# UpperMotor.net
KiCad netlist of a schematic drawn in EasyEDA Pro
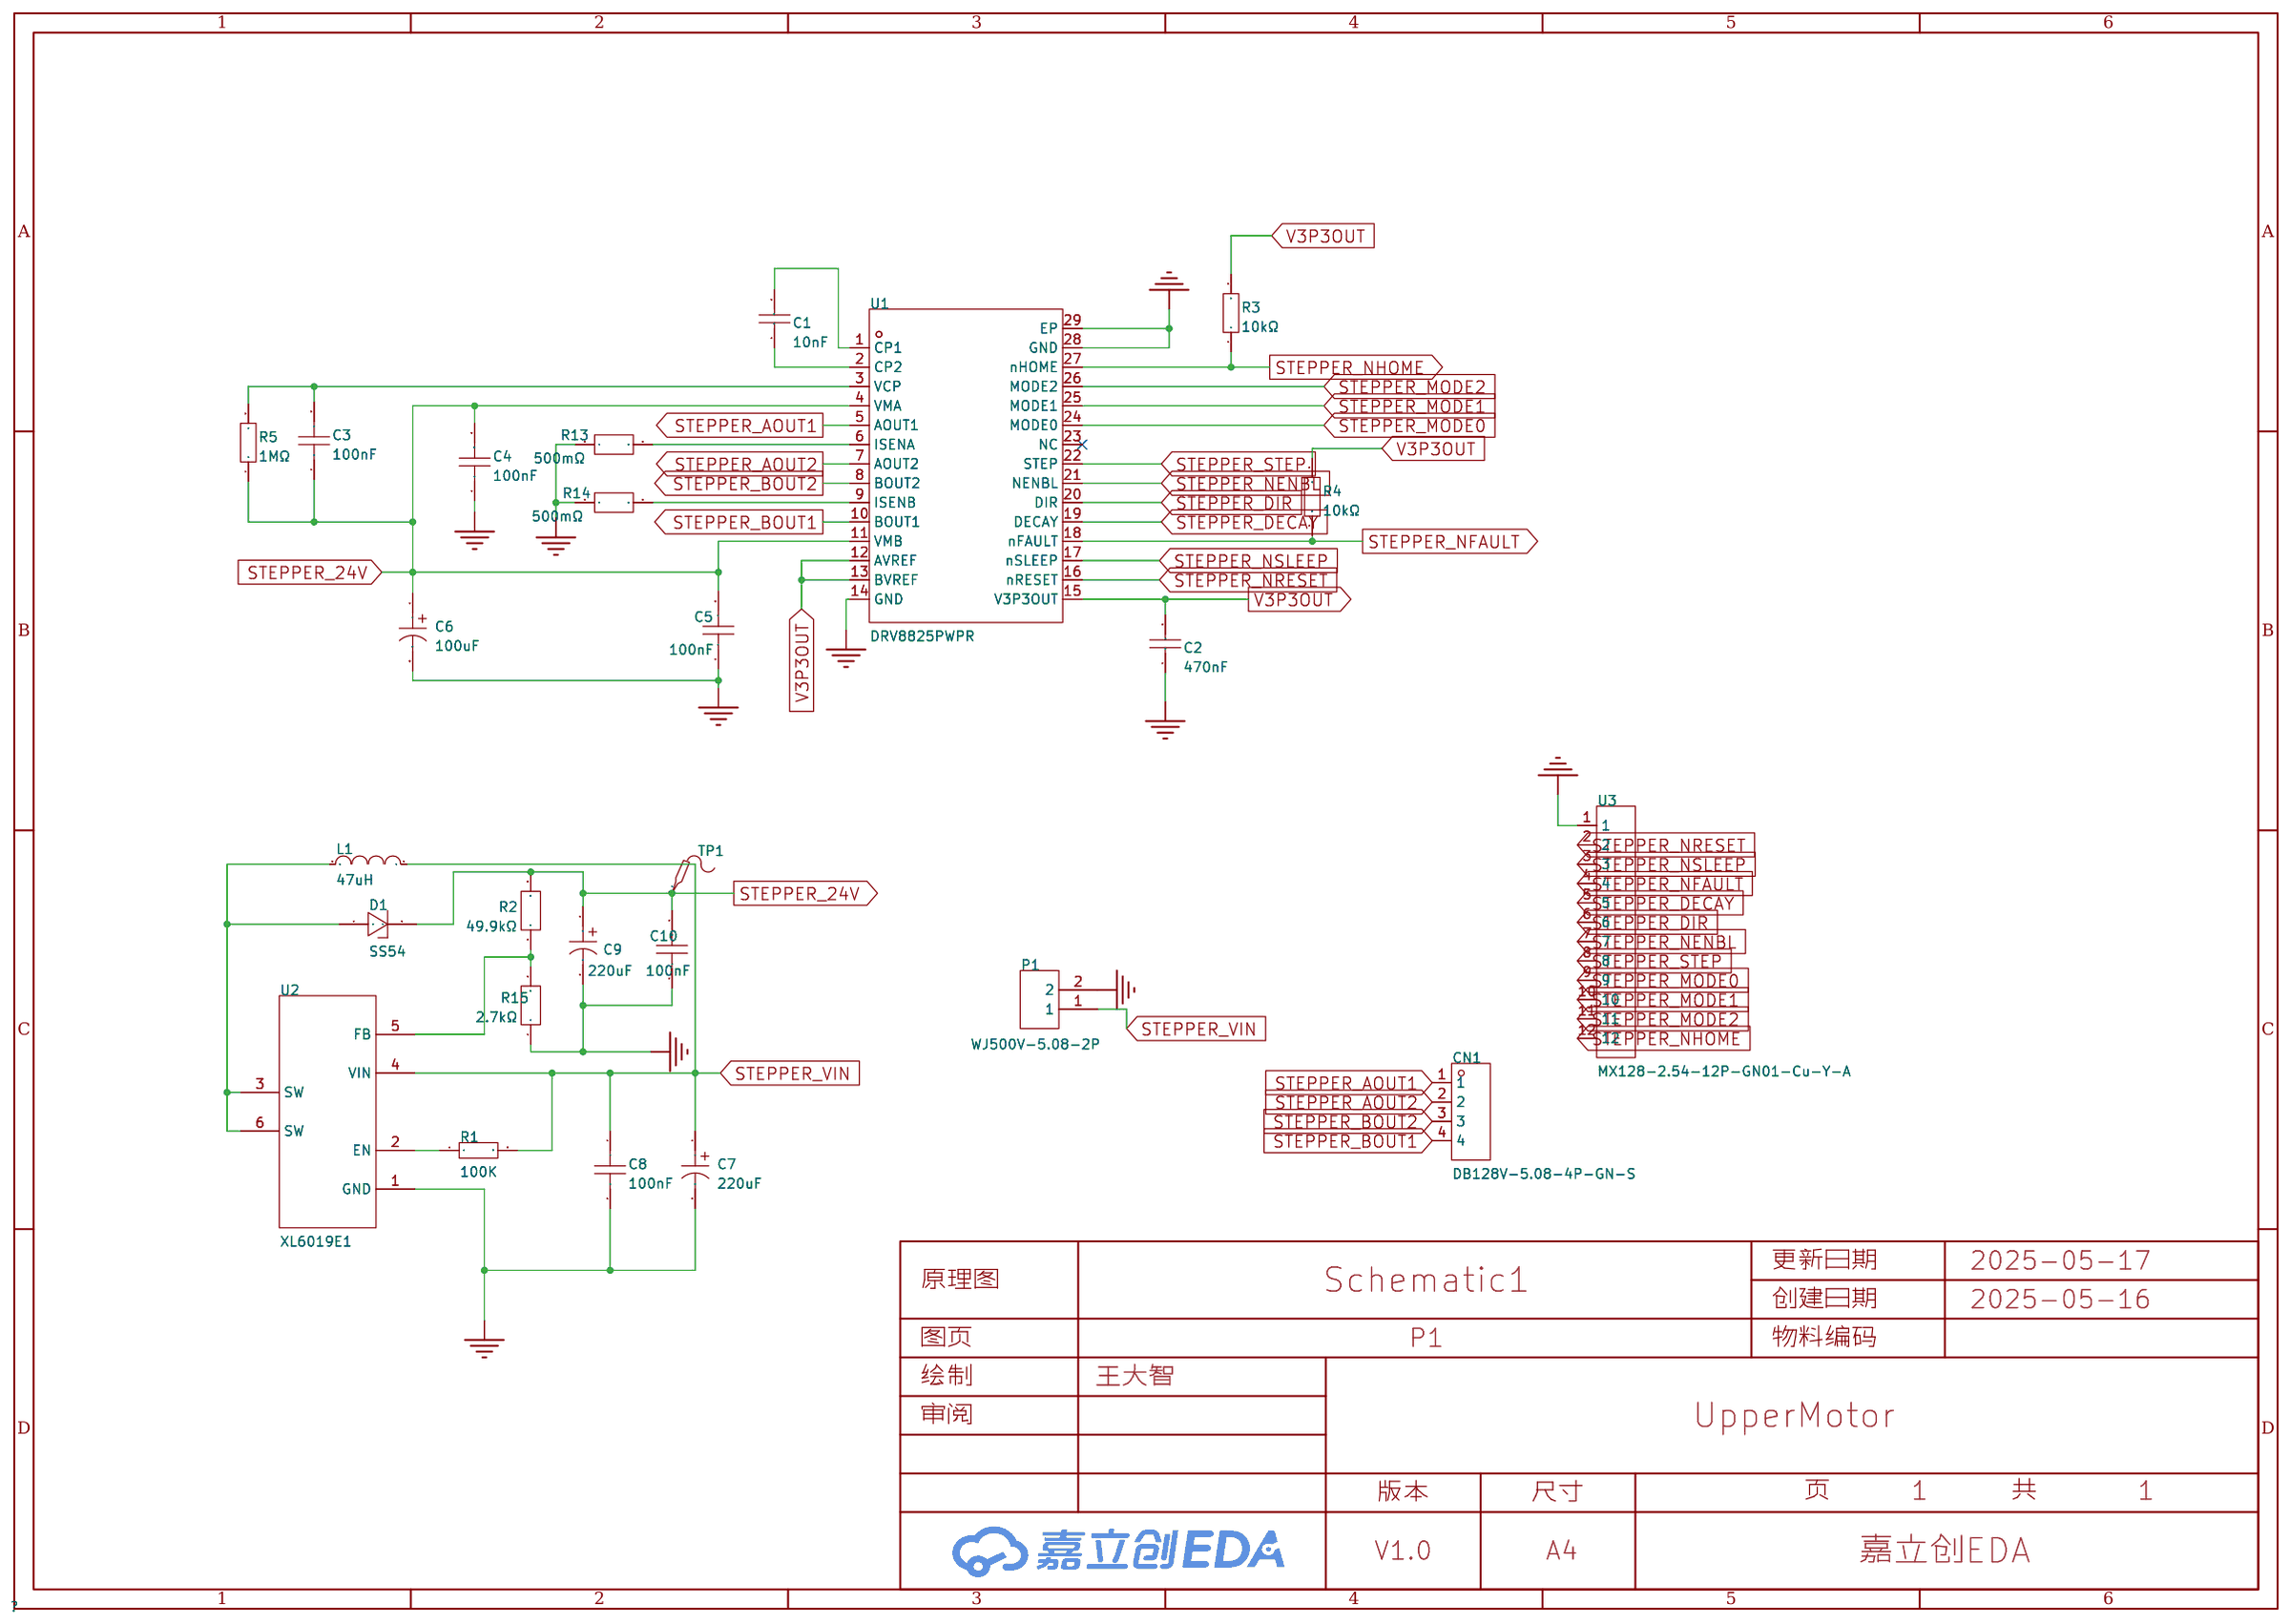
[diagram p0: schematic sheet]

(export (version "E")
  (design (tool "Eeschema 10.0.6"))
  (components
    (comp (ref "C1")
      (value "10nF")
      (footprint "easyedapro:C0603")
      (description "容值:10nF;精度:±10%;额定电压:50V;材质(温度系数):X7R;")
      (fields
        (field (name "Manufacturer Part") "CL10B103KB8NNNC")
        (field (name "Manufacturer") "SAMSUNG(三星)")
      )
      (libsource (lib "easyedapro") (part "CL10B103KB8NNNC"))
    )
    (comp (ref "C2")
      (value "470nF")
      (footprint "easyedapro:C0603")
      (description "容值:470nF;精度:±10%;额定电压:25V;材质(温度系数):X7R;")
      (fields
        (field (name "Manufacturer Part") "CL10B474KA8NNNC")
        (field (name "Manufacturer") "SAMSUNG(三星)")
      )
      (libsource (lib "easyedapro") (part "CL10B474KA8NNNC"))
    )
    (comp (ref "C3")
      (value "100nF")
      (footprint "easyedapro:C0603")
      (description "容值:100nF;精度:±10%;额定电压:50V;温度系数:X7R;")
      (fields
        (field (name "Manufacturer Part") "CGA0603X7R104K500JT")
        (field (name "Manufacturer") "HRE(芯声)")
      )
      (libsource (lib "easyedapro") (part "CGA0603X7R104K500JT"))
    )
    (comp (ref "C4")
      (value "100nF")
      (footprint "easyedapro:C0603")
      (description "容值:100nF;精度:±10%;额定电压:50V;温度系数:X7R;")
      (fields
        (field (name "Manufacturer Part") "CGA0603X7R104K500JT")
        (field (name "Manufacturer") "HRE(芯声)")
      )
      (libsource (lib "easyedapro") (part "CGA0603X7R104K500JT"))
    )
    (comp (ref "C5")
      (value "100nF")
      (footprint "easyedapro:C0603")
      (description "容值:100nF;精度:±10%;额定电压:50V;温度系数:X7R;")
      (fields
        (field (name "Manufacturer Part") "CGA0603X7R104K500JT")
        (field (name "Manufacturer") "HRE(芯声)")
      )
      (libsource (lib "easyedapro") (part "CGA0603X7R104K500JT"))
    )
    (comp (ref "C6")
      (value "100uF")
      (footprint "easyedapro:CAP-SMD_BD8.1-L8.3-W8.3-LS9.3-FD")
      (description "容值:100uF;精度:±20%;额定电压:50V;纹波电流:300mA@100kHz;等效串联电阻:600mΩ@100kHz;")
      (fields
        (field (name "Manufacturer Part") "GVE1H107M0810CNVC")
        (field (name "Manufacturer") "HRK(鸿瑞凯电子)")
      )
      (libsource (lib "easyedapro") (part "GVE1H107M0810CNVC"))
    )
    (comp (ref "C7")
      (value "220uF")
      (footprint "easyedapro:CAP-SMD_BD8.0-L8.3-W8.3-FD")
      (description "容值:220uF;精度:±20%;额定电压:35V;纹波电流:175mA@120Hz;")
      (fields
        (field (name "Manufacturer Part") "GVT1V227M0810CNVC")
        (field (name "Manufacturer") "HRK(鸿瑞凯电子)")
      )
      (libsource (lib "easyedapro") (part "GVT1V227M0810CNVC"))
    )
    (comp (ref "C8")
      (value "100nF")
      (footprint "easyedapro:C0603")
      (libsource (lib "easyedapro") (part "CapAcitance"))
    )
    (comp (ref "C9")
      (value "220uF")
      (footprint "easyedapro:CAP-SMD_BD8.0-L8.3-W8.3-FD")
      (description "容值:220uF;精度:±20%;额定电压:35V;纹波电流:175mA@120Hz;")
      (fields
        (field (name "Manufacturer Part") "GVT1V227M0810CNVC")
        (field (name "Manufacturer") "HRK(鸿瑞凯电子)")
      )
      (libsource (lib "easyedapro") (part "GVT1V227M0810CNVC"))
    )
    (comp (ref "C10")
      (value "100nF")
      (footprint "easyedapro:C0603")
      (libsource (lib "easyedapro") (part "CapAcitance"))
    )
    (comp (ref "CN1")
      (value "DB128V-5.08-4P-GN-S")
      (footprint "easyedapro:CONN-TH_4P-P5.08_DIBO_DB128V-5.08")
      (fields (field (name "Manufacturer") "DORABO(地博电气)"))
      (libsource (lib "easyedapro") (part "DB128V-5.08-4P-GN-S"))
    )
    (comp (ref "D1")
      (value "SS54")
      (footprint "easyedapro:SMA_L4.3-W2.6-LS5.0-FD")
      (description "二极管配置:独立式;正向压降(Vf):550mV@5.0A;直流反向耐压(Vr):40V;整流电流:5A;")
      (fields (field (name "Manufacturer") "宏迦橙"))
      (libsource (lib "easyedapro") (part "SS54_C7420369"))
    )
    (comp (ref "L1")
      (value "47uH")
      (footprint "easyedapro:IND-SMD_L11.5-W10.0_SMMS1040")
      (description "电感值:47uH;精度:±20%;额定电流:3A;饱和电流(Isat):4.5A;类型:一体成型电感;")
      (fields (field (name "Manufacturer Part") "SMMS1040-470M") (field (name "Manufacturer") "SXN(顺翔诺)"))
      (libsource (lib "easyedapro") (part "SMMS1040-470M"))
    )
    (comp (ref "P1")
      (value "WJ500V-5.08-2P")
      (footprint "easyedapro:CONN-TH_2P-P5.00_WJ500V-5.08-2P")
      (fields (field (name "Manufacturer") "KANGNEX(康奈克斯电气)"))
      (libsource (lib "easyedapro") (part "WJ500V-5.08-2P-14-00A"))
    )
    (comp (ref "R1") (value "100K") (footprint "easyedapro:R0603") (libsource (lib "easyedapro") (part "电阻")))
    (comp (ref "R2")
      (value "49.9kΩ")
      (footprint "easyedapro:R0603")
      (description "电阻类型:厚膜电阻;阻值:49.9kΩ;精度:±1%;功率:100mW;最大工作电压:75V;温度系数:±100ppm/°C;")
      (fields (field (name "Manufacturer Part") "FRC0603F4992TS") (field (name "Manufacturer") "FOJAN(富捷)"))
      (libsource (lib "easyedapro") (part "FRC0603F4992TS"))
    )
    (comp (ref "R3")
      (value "10kΩ")
      (footprint "easyedapro:R0603")
      (description "电阻类型:厚膜电阻;阻值:10kΩ;精度:±1%;功率:100mW;最大工作电压:75V;温度系数:±100ppm/°C;")
      (fields (field (name "Manufacturer Part") "RC0603FR-0710KL") (field (name "Manufacturer") "YAGEO(国巨)"))
      (libsource (lib "easyedapro") (part "RC0603FR-0710KL"))
    )
    (comp (ref "R4")
      (value "10kΩ")
      (footprint "easyedapro:R0603")
      (description "电阻类型:厚膜电阻;阻值:10kΩ;精度:±1%;功率:100mW;最大工作电压:75V;温度系数:±100ppm/°C;")
      (fields (field (name "Manufacturer Part") "RC0603FR-0710KL") (field (name "Manufacturer") "YAGEO(国巨)"))
      (libsource (lib "easyedapro") (part "RC0603FR-0710KL"))
    )
    (comp (ref "R5")
      (value "1MΩ")
      (footprint "easyedapro:R0603")
      (fields
        (field (name "Manufacturer Part") "0603WAF1004T5E")
        (field (name "Manufacturer") "UNI-ROYAL(厚声)")
      )
      (libsource (lib "easyedapro") (part "电阻"))
    )
    (comp (ref "R13")
      (value "500mΩ")
      (footprint "easyedapro:R0603")
      (description "电阻类型:厚膜电阻;阻值:500mΩ;精度:±5%;功率:100mW;最大工作电压:100V;温度系数:±300ppm/°C;")
      (fields (field (name "Manufacturer Part") "FRL0603JR500TS") (field (name "Manufacturer") "FOJAN(富捷)"))
      (libsource (lib "easyedapro") (part "FRL0603JR500TS"))
    )
    (comp (ref "R14")
      (value "500mΩ")
      (footprint "easyedapro:R0603")
      (description "电阻类型:厚膜电阻;阻值:500mΩ;精度:±5%;功率:100mW;最大工作电压:100V;温度系数:±300ppm/°C;")
      (fields (field (name "Manufacturer Part") "FRL0603JR500TS") (field (name "Manufacturer") "FOJAN(富捷)"))
      (libsource (lib "easyedapro") (part "FRL0603JR500TS"))
    )
    (comp (ref "R15")
      (value "2.7kΩ")
      (footprint "easyedapro:R0603")
      (description "电阻类型:厚膜电阻;阻值:2.7kΩ;精度:±1%;功率:100mW;工作电压:75V;温度系数:±100ppm/°C;")
      (fields (field (name "Manufacturer Part") "FRC0603F2701TS") (field (name "Manufacturer") "FOJAN(富捷)"))
      (libsource (lib "easyedapro") (part "FRC0603F2701TS"))
    )
    (comp (ref "TP1")
      (value "~")
      (footprint "easyedapro:Test-Point-0.5mm")
      (description "Test Point 测试点")
      (libsource (lib "easyedapro") (part "Test-Point"))
    )
    (comp (ref "U1")
      (value "DRV8825PWPR")
      (footprint "easyedapro:HTSSOP-28_L9.7-W4.4-P0.65-LS6.4-BL-EP")
      (description "DRV8825 具有电流调节功能和 1/32 微步进的 45V、2.5A 双极步进电机驱动器")
      (fields (field (name "Manufacturer") "TI(德州仪器)"))
      (libsource (lib "easyedapro") (part "DRV8825PWPR"))
    )
    (comp (ref "U2")
      (value "XL6019E1")
      (footprint "easyedapro:TO-263-5_L10.2-W9.9-P1.70-LS14.4-TL")
      (description "功能类型:升降压型;输出类型:可调;工作电压:5V~40V;输出电压:-;输出电流:5A;")
      (fields (field (name "Manufacturer") "XLSEMI(芯龙)"))
      (libsource (lib "easyedapro") (part "XL6019E1"))
    )
    (comp (ref "U3")
      (value "MX128-2.54-12P-GN01-Cu-Y-A")
      (footprint "easyedapro:CONN-TH_12P-P2.54_MX128-2.54-12P-GN01-CU-Y-A")
      (fields (field (name "Manufacturer") "MAX(迈旭)"))
      (libsource (lib "easyedapro") (part "MX128-2.54-12P-GN01-CU-Y-A"))
    )
  )
  (nets
    (net (code "1") (name "GND") (class "Default")
      (node (ref "C10") (pin "1") (pinfunction "1_1") (pintype "input"))
      (node (ref "C2") (pin "1") (pinfunction "1_1") (pintype "input"))
      (node (ref "C4") (pin "1") (pinfunction "1_1") (pintype "unspecified"))
      (node (ref "C5") (pin "1") (pinfunction "1_1") (pintype "unspecified"))
      (node (ref "C6") (pin "2") (pinfunction "2_2") (pintype "input"))
      (node (ref "C7") (pin "2") (pinfunction "2_2") (pintype "input"))
      (node (ref "C8") (pin "2") (pinfunction "2_2") (pintype "input"))
      (node (ref "C9") (pin "2") (pinfunction "2_2") (pintype "input"))
      (node (ref "P1") (pin "2") (pinfunction "2_2") (pintype "unspecified"))
      (node (ref "R13") (pin "1") (pinfunction "1_1") (pintype "unspecified"))
      (node (ref "R14") (pin "1") (pinfunction "1_1") (pintype "unspecified"))
      (node (ref "R15") (pin "1") (pinfunction "1_1") (pintype "unspecified"))
      (node (ref "U1") (pin "14") (pinfunction "GND_14") (pintype "unspecified"))
      (node (ref "U1") (pin "28") (pinfunction "GND_28") (pintype "unspecified"))
      (node (ref "U1") (pin "29") (pinfunction "EP_29") (pintype "unspecified"))
      (node (ref "U2") (pin "1") (pinfunction "GND_1") (pintype "unspecified"))
      (node (ref "U3") (pin "1") (pinfunction "1_1") (pintype "unspecified"))
    )
    (net (code "2") (name "Net-(D1-A)") (class "Default")
      (node (ref "D1") (pin "1") (pinfunction "A_1") (pintype "unspecified"))
      (node (ref "L1") (pin "1") (pinfunction "1_1") (pintype "unspecified"))
      (node (ref "U2") (pin "3") (pinfunction "SW_3") (pintype "unspecified"))
      (node (ref "U2") (pin "6") (pinfunction "SW_6") (pintype "unspecified"))
    )
    (net (code "3") (name "Net-(U1-CP1)") (class "Default")
      (node (ref "C1") (pin "2") (pinfunction "2_2") (pintype "input"))
      (node (ref "U1") (pin "1") (pinfunction "CP1_1") (pintype "unspecified"))
    )
    (net (code "4") (name "Net-(U1-CP2)") (class "Default")
      (node (ref "C1") (pin "1") (pinfunction "1_1") (pintype "input"))
      (node (ref "U1") (pin "2") (pinfunction "CP2_2") (pintype "unspecified"))
    )
    (net (code "5") (name "Net-(U1-ISENA)") (class "Default")
      (node (ref "R13") (pin "2") (pinfunction "2_2") (pintype "unspecified"))
      (node (ref "U1") (pin "6") (pinfunction "ISENA_6") (pintype "unspecified"))
    )
    (net (code "6") (name "Net-(U1-ISENB)") (class "Default")
      (node (ref "R14") (pin "2") (pinfunction "2_2") (pintype "unspecified"))
      (node (ref "U1") (pin "9") (pinfunction "ISENB_9") (pintype "unspecified"))
    )
    (net (code "7") (name "Net-(U1-VCP)") (class "Default")
      (node (ref "C3") (pin "2") (pinfunction "2_2") (pintype "unspecified"))
      (node (ref "R5") (pin "2") (pinfunction "2_2") (pintype "input"))
      (node (ref "U1") (pin "3") (pinfunction "VCP_3") (pintype "unspecified"))
    )
    (net (code "8") (name "Net-(U2-EN)") (class "Default")
      (node (ref "R1") (pin "1") (pinfunction "1_1") (pintype "input"))
      (node (ref "U2") (pin "2") (pinfunction "EN_2") (pintype "unspecified"))
    )
    (net (code "9") (name "Net-(U2-FB)") (class "Default")
      (node (ref "R15") (pin "2") (pinfunction "2_2") (pintype "unspecified"))
      (node (ref "R2") (pin "1") (pinfunction "1_1") (pintype "unspecified"))
      (node (ref "U2") (pin "5") (pinfunction "FB_5") (pintype "unspecified"))
    )
    (net (code "10") (name "STEPPER_24V") (class "Default")
      (node (ref "C10") (pin "2") (pinfunction "2_2") (pintype "input"))
      (node (ref "C3") (pin "1") (pinfunction "1_1") (pintype "unspecified"))
      (node (ref "C4") (pin "2") (pinfunction "2_2") (pintype "unspecified"))
      (node (ref "C5") (pin "2") (pinfunction "2_2") (pintype "unspecified"))
      (node (ref "C6") (pin "1") (pinfunction "1_1") (pintype "input"))
      (node (ref "C9") (pin "1") (pinfunction "1_1") (pintype "input"))
      (node (ref "D1") (pin "2") (pinfunction "K_2") (pintype "unspecified"))
      (node (ref "R2") (pin "2") (pinfunction "2_2") (pintype "unspecified"))
      (node (ref "R5") (pin "1") (pinfunction "1_1") (pintype "input"))
      (node (ref "TP1") (pin "1") (pinfunction "1_1") (pintype "input"))
      (node (ref "U1") (pin "11") (pinfunction "VMB_11") (pintype "unspecified"))
      (node (ref "U1") (pin "4") (pinfunction "VMA_4") (pintype "unspecified"))
    )
    (net (code "11") (name "STEPPER_AOUT1") (class "Default")
      (node (ref "CN1") (pin "1") (pinfunction "1_1") (pintype "unspecified"))
      (node (ref "U1") (pin "5") (pinfunction "AOUT1_5") (pintype "unspecified"))
    )
    (net (code "12") (name "STEPPER_AOUT2") (class "Default")
      (node (ref "CN1") (pin "2") (pinfunction "2_2") (pintype "unspecified"))
      (node (ref "U1") (pin "7") (pinfunction "AOUT2_7") (pintype "unspecified"))
    )
    (net (code "13") (name "STEPPER_BOUT1") (class "Default")
      (node (ref "CN1") (pin "4") (pinfunction "4_4") (pintype "unspecified"))
      (node (ref "U1") (pin "10") (pinfunction "BOUT1_10") (pintype "unspecified"))
    )
    (net (code "14") (name "STEPPER_BOUT2") (class "Default")
      (node (ref "CN1") (pin "3") (pinfunction "3_3") (pintype "unspecified"))
      (node (ref "U1") (pin "8") (pinfunction "BOUT2_8") (pintype "unspecified"))
    )
    (net (code "15") (name "STEPPER_DECAY") (class "Default")
      (node (ref "U1") (pin "19") (pinfunction "DECAY_19") (pintype "unspecified"))
      (node (ref "U3") (pin "5") (pinfunction "5_5") (pintype "unspecified"))
    )
    (net (code "16") (name "STEPPER_DIR") (class "Default")
      (node (ref "U1") (pin "20") (pinfunction "DIR_20") (pintype "unspecified"))
      (node (ref "U3") (pin "6") (pinfunction "6_6") (pintype "unspecified"))
    )
    (net (code "17") (name "STEPPER_MODE0") (class "Default")
      (node (ref "U1") (pin "24") (pinfunction "MODE0_24") (pintype "unspecified"))
      (node (ref "U3") (pin "9") (pinfunction "9_9") (pintype "unspecified"))
    )
    (net (code "18") (name "STEPPER_MODE1") (class "Default")
      (node (ref "U1") (pin "25") (pinfunction "MODE1_25") (pintype "unspecified"))
      (node (ref "U3") (pin "10") (pinfunction "10_10") (pintype "unspecified"))
    )
    (net (code "19") (name "STEPPER_MODE2") (class "Default")
      (node (ref "U1") (pin "26") (pinfunction "MODE2_26") (pintype "unspecified"))
      (node (ref "U3") (pin "11") (pinfunction "11_11") (pintype "unspecified"))
    )
    (net (code "20") (name "STEPPER_NENBL") (class "Default")
      (node (ref "U1") (pin "21") (pinfunction "NENBL_21") (pintype "unspecified"))
      (node (ref "U3") (pin "7") (pinfunction "7_7") (pintype "unspecified"))
    )
    (net (code "21") (name "STEPPER_NFAULT") (class "Default")
      (node (ref "R4") (pin "1") (pinfunction "1_1") (pintype "input"))
      (node (ref "U1") (pin "18") (pinfunction "nFAULT_18") (pintype "unspecified"))
      (node (ref "U3") (pin "4") (pinfunction "4_4") (pintype "unspecified"))
    )
    (net (code "22") (name "STEPPER_NHOME") (class "Default")
      (node (ref "R3") (pin "1") (pinfunction "1_1") (pintype "input"))
      (node (ref "U1") (pin "27") (pinfunction "nHOME_27") (pintype "unspecified"))
      (node (ref "U3") (pin "12") (pinfunction "12_12") (pintype "unspecified"))
    )
    (net (code "23") (name "STEPPER_NRESET") (class "Default")
      (node (ref "U1") (pin "16") (pinfunction "nRESET_16") (pintype "unspecified"))
      (node (ref "U3") (pin "2") (pinfunction "2_2") (pintype "unspecified"))
    )
    (net (code "24") (name "STEPPER_NSLEEP") (class "Default")
      (node (ref "U1") (pin "17") (pinfunction "nSLEEP_17") (pintype "unspecified"))
      (node (ref "U3") (pin "3") (pinfunction "3_3") (pintype "unspecified"))
    )
    (net (code "25") (name "STEPPER_STEP") (class "Default")
      (node (ref "U1") (pin "22") (pinfunction "STEP_22") (pintype "unspecified"))
      (node (ref "U3") (pin "8") (pinfunction "8_8") (pintype "unspecified"))
    )
    (net (code "26") (name "STEPPER_VIN") (class "Default")
      (node (ref "C7") (pin "1") (pinfunction "1_1") (pintype "input"))
      (node (ref "C8") (pin "1") (pinfunction "1_1") (pintype "input"))
      (node (ref "L1") (pin "2") (pinfunction "2_2") (pintype "unspecified"))
      (node (ref "P1") (pin "1") (pinfunction "1_1") (pintype "unspecified"))
      (node (ref "R1") (pin "2") (pinfunction "2_2") (pintype "input"))
      (node (ref "U2") (pin "4") (pinfunction "VIN_4") (pintype "unspecified"))
    )
    (net (code "27") (name "V3P3OUT") (class "Default")
      (node (ref "C2") (pin "2") (pinfunction "2_2") (pintype "input"))
      (node (ref "R3") (pin "2") (pinfunction "2_2") (pintype "input"))
      (node (ref "R4") (pin "2") (pinfunction "2_2") (pintype "input"))
      (node (ref "U1") (pin "12") (pinfunction "AVREF_12") (pintype "unspecified"))
      (node (ref "U1") (pin "13") (pinfunction "BVREF_13") (pintype "unspecified"))
      (node (ref "U1") (pin "15") (pinfunction "V3P3OUT_15") (pintype "unspecified"))
    )
    (net (code "28") (name "unconnected-(U1-NC-Pad23)") (class "Default")
      (node (ref "U1") (pin "23") (pinfunction "NC_23") (pintype "unspecified+no_connect"))
    )
  )
)
